# oshcamp23-badge-RevA2.net
KiCad netlist of a schematic drawn in EAGLE
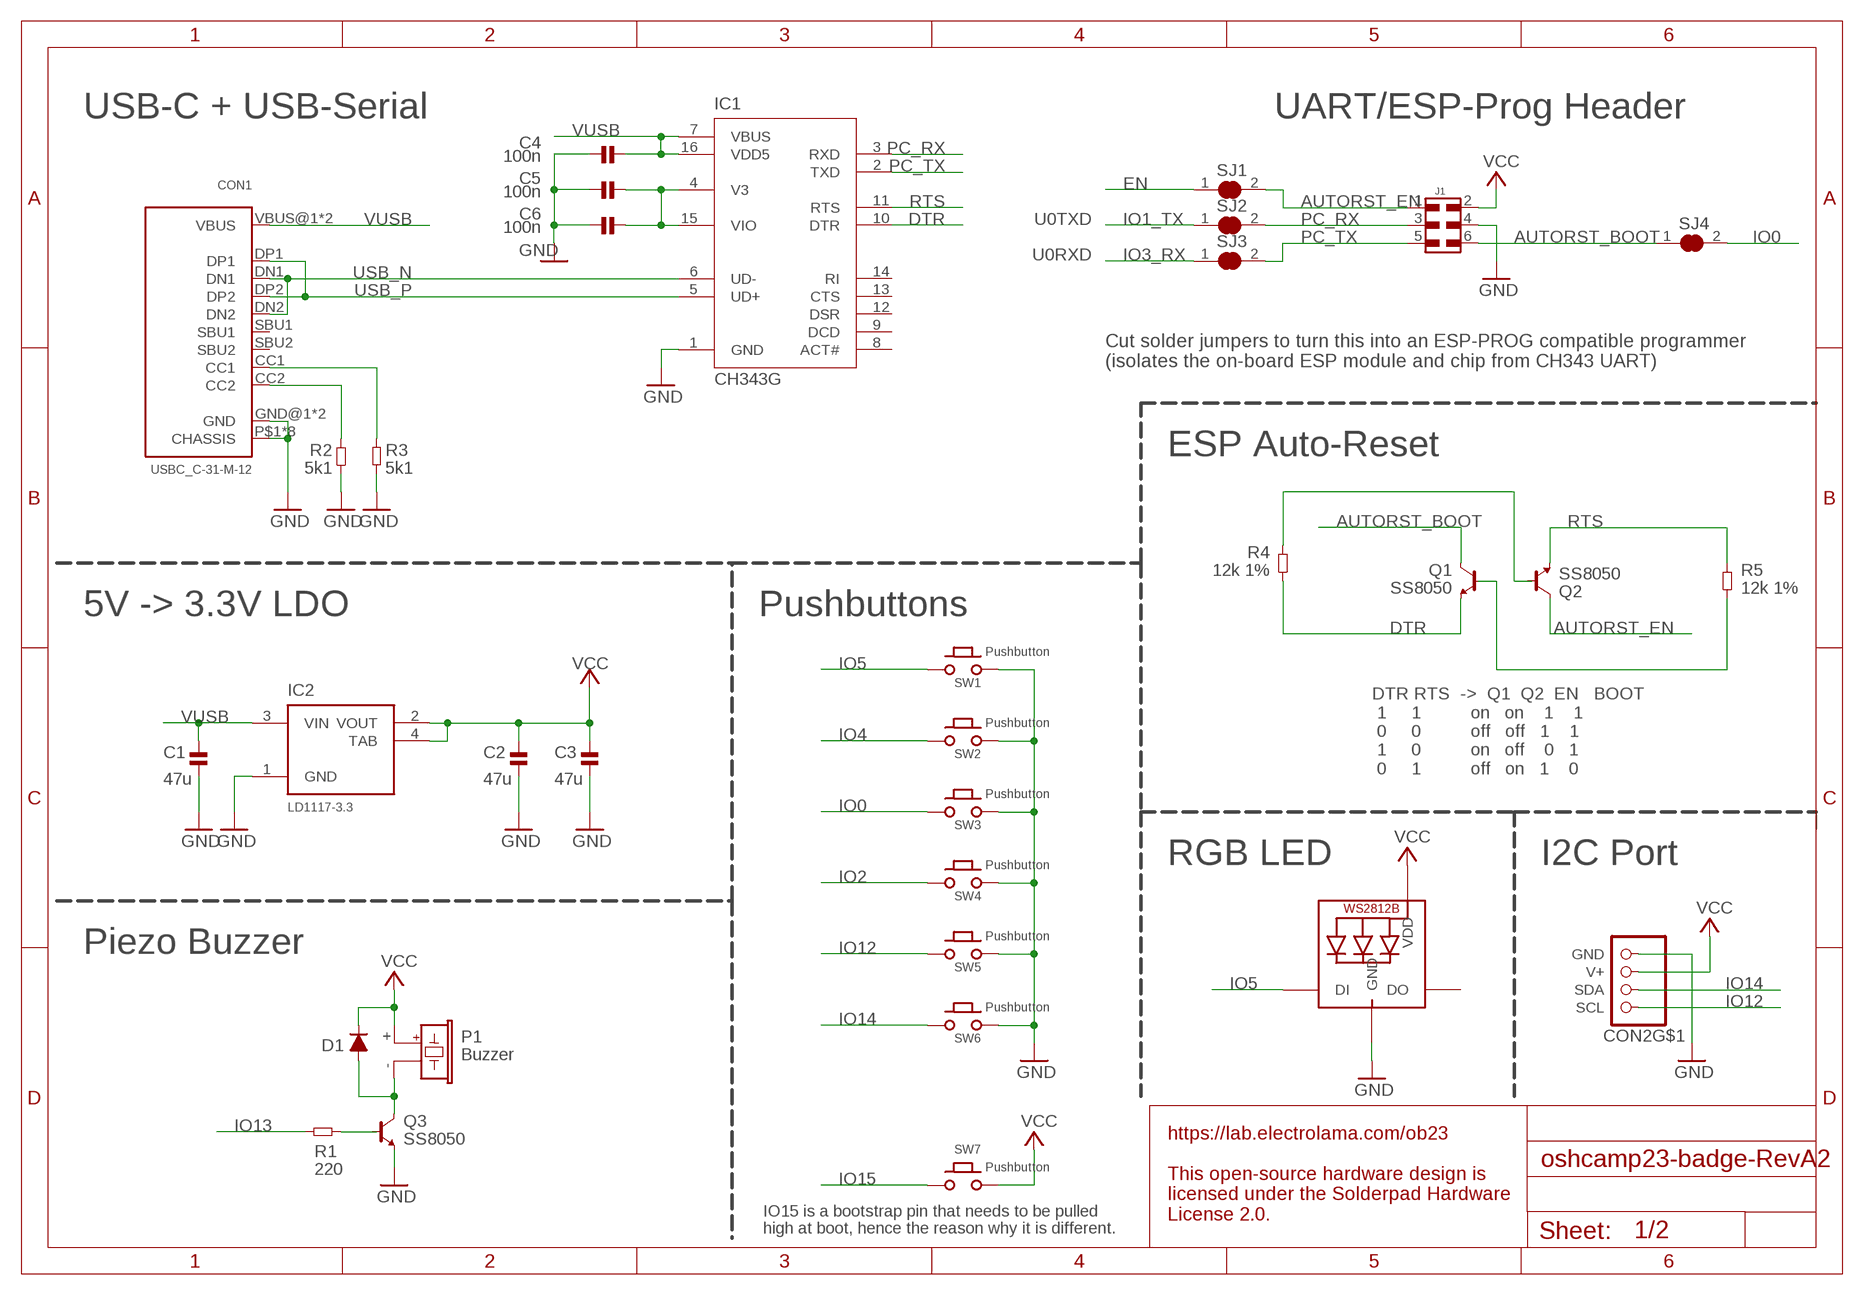
[diagram p0: schematic, sheet 1]
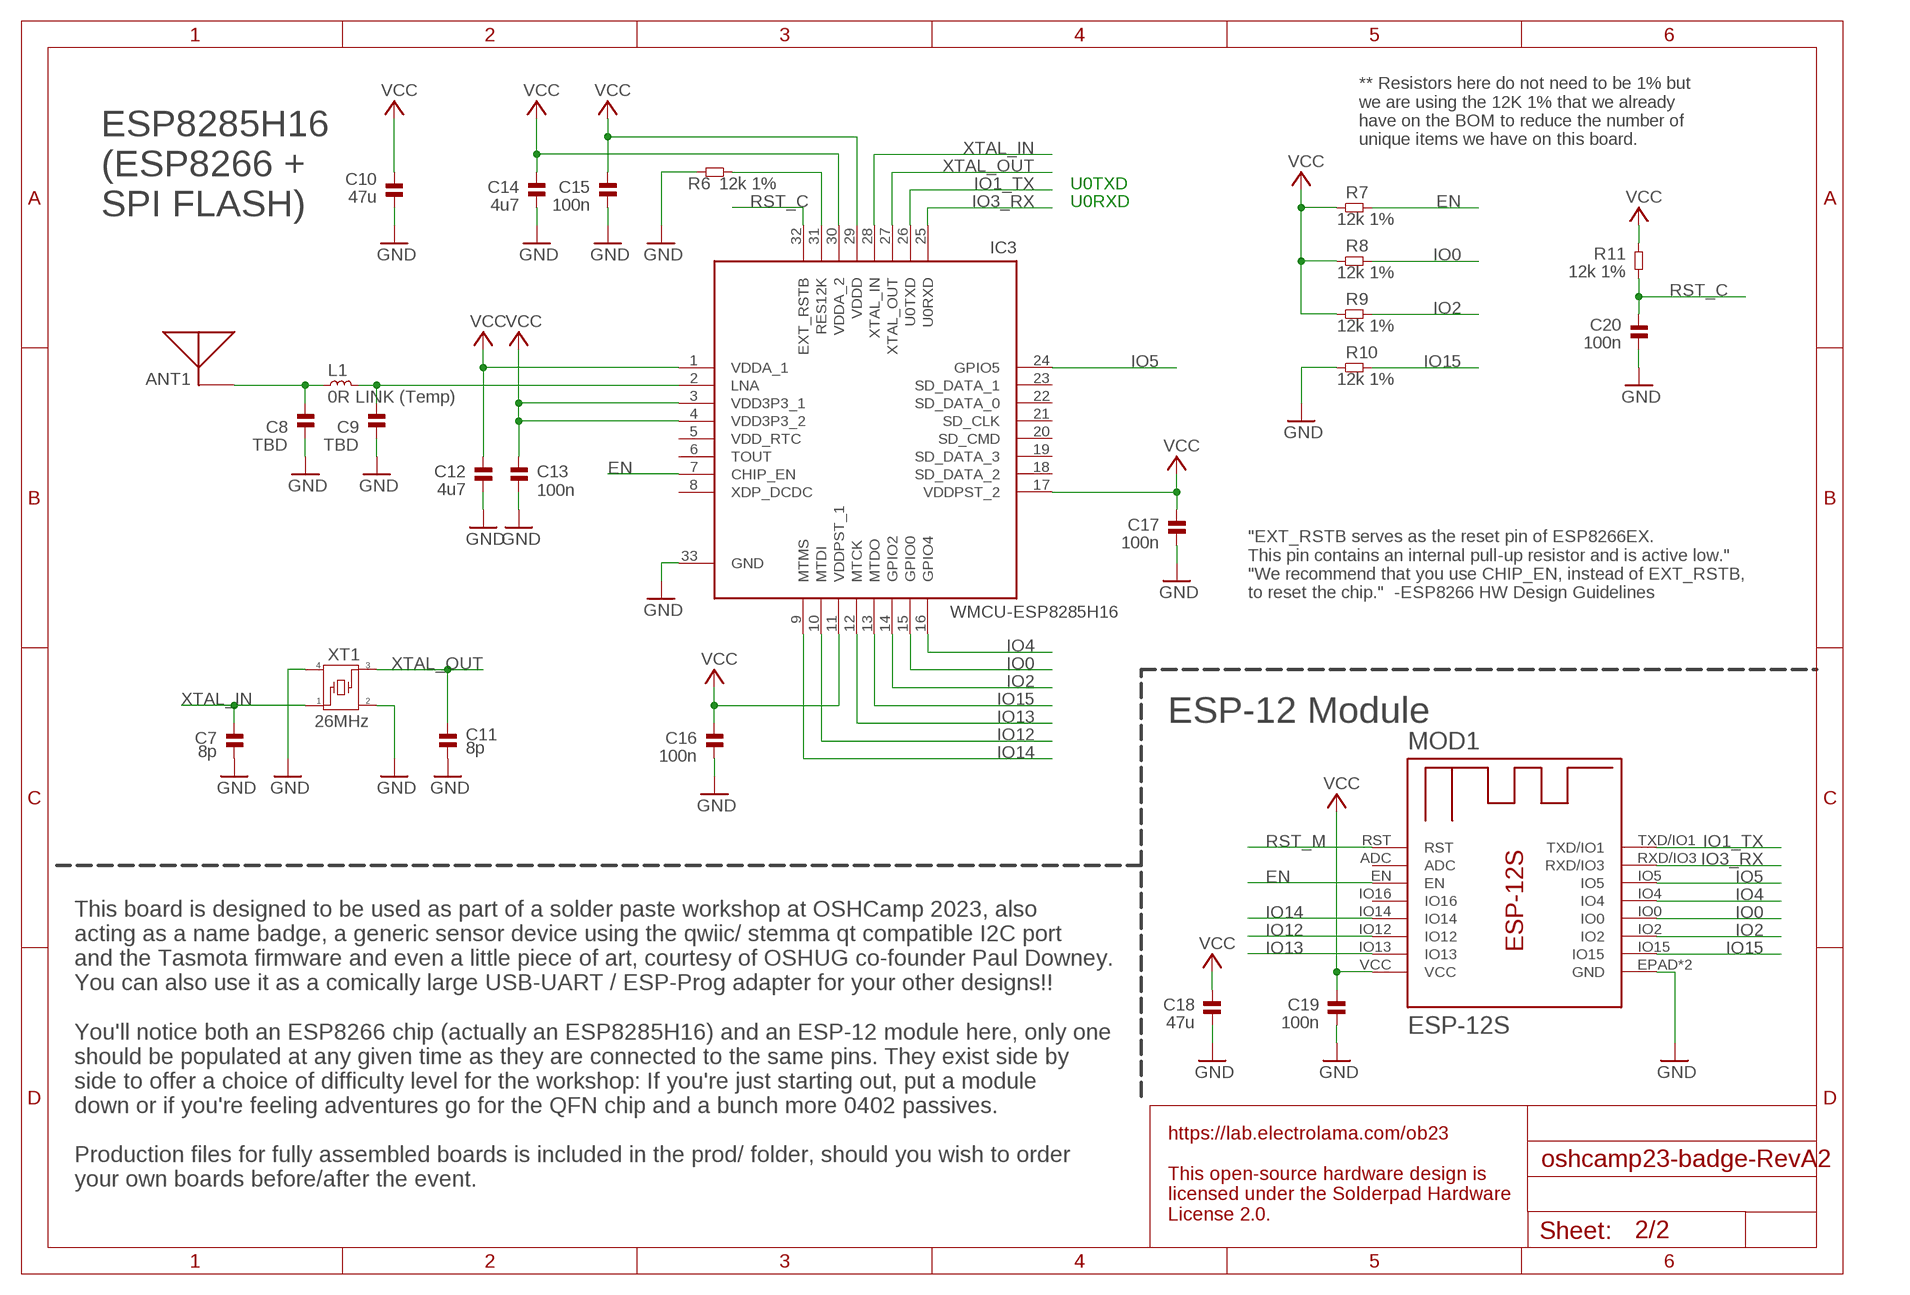
[diagram p1: schematic, sheet 2]

(export (version "E")
  (design (tool "Eeschema 10.0.6"))
  (components
    (comp (ref "C1")
      (value "47u")
      (footprint "eagle-import:_PKG_C_1206")
      (fields (field (name "MPN") "CL31A476MPHNNNE"))
      (libsource (lib "eagle-import") (part "CAP-1206"))
    )
    (comp (ref "C2")
      (value "47u")
      (footprint "eagle-import:_PKG_C_1206")
      (fields (field (name "MPN") "CL31A476MPHNNNE"))
      (libsource (lib "eagle-import") (part "CAP-1206"))
    )
    (comp (ref "C3")
      (value "47u")
      (footprint "eagle-import:_PKG_C_1206")
      (fields (field (name "MPN") "CL31A476MPHNNNE"))
      (libsource (lib "eagle-import") (part "CAP-1206"))
    )
    (comp (ref "C4")
      (value "100n")
      (footprint "eagle-import:_PKG_C_0402")
      (libsource (lib "eagle-import") (part "CAP-0402"))
    )
    (comp (ref "C5")
      (value "100n")
      (footprint "eagle-import:_PKG_C_0402")
      (libsource (lib "eagle-import") (part "CAP-0402"))
    )
    (comp (ref "C6")
      (value "100n")
      (footprint "eagle-import:_PKG_C_0402")
      (libsource (lib "eagle-import") (part "CAP-0402"))
    )
    (comp (ref "CON1")
      (value "USBC_C-31-M-12")
      (footprint "eagle-import:USBC_C-31-M-12")
      (libsource (lib "eagle-import") (part "USBC_USB-C-12"))
    )
    (comp (ref "CON2")
      (value "STEMMA_I2C_QT")
      (footprint "eagle-import:JST_SH4")
      (libsource (lib "eagle-import") (part "STEMMA_I2C_QT"))
    )
    (comp (ref "D1")
      (value "DIODE-SWITCHING-1N4148W")
      (footprint "eagle-import:_PKG_SOD123")
      (libsource (lib "eagle-import") (part "DIODE-SWITCHING-1N4148W"))
    )
    (comp (ref "IC1")
      (value "CH343G")
      (footprint "eagle-import:_PKG_SOP16")
      (libsource (lib "eagle-import") (part "INTERFACE-CH343G"))
    )
    (comp (ref "IC2")
      (value "LD1117-3.3")
      (footprint "eagle-import:_PKG_SOT223-4_TI-DCY4")
      (libsource (lib "eagle-import") (part "POWER-LDO-LD1117-SOT223-4"))
    )
    (comp (ref "J1")
      (value "61030621121")
      (footprint "eagle-import:61030621121")
      (libsource (lib "eagle-import") (part "6103XX21121_61030621121"))
    )
    (comp (ref "LED1")
      (value "WS2812B5050")
      (footprint "eagle-import:WS2812B")
      (libsource (lib "eagle-import") (part "WS2812B5050"))
    )
    (comp (ref "P1")
      (value "Buzzer")
      (footprint "eagle-import:MLT-8530")
      (libsource (lib "eagle-import") (part "PIEZO-MLT-8530"))
    )
    (comp (ref "Q1")
      (value "SS8050")
      (footprint "eagle-import:SOT96P237X111-3N")
      (fields
        (field (name "ARROW_PART_NUMBER") "MMBT5550LT1G")
        (field (name "MOUSER_PART_NUMBER") "863-MMBT5550LT1G")
      )
      (libsource (lib "eagle-import") (part "NPN-MMBT5550LT1G"))
    )
    (comp (ref "Q2")
      (value "SS8050")
      (footprint "eagle-import:SOT96P237X111-3N")
      (fields
        (field (name "ARROW_PART_NUMBER") "MMBT5550LT1G")
        (field (name "MOUSER_PART_NUMBER") "863-MMBT5550LT1G")
      )
      (libsource (lib "eagle-import") (part "NPN-MMBT5550LT1G"))
    )
    (comp (ref "Q3")
      (value "SS8050")
      (footprint "eagle-import:SOT96P237X111-3N")
      (fields
        (field (name "ARROW_PART_NUMBER") "MMBT5550LT1G")
        (field (name "MOUSER_PART_NUMBER") "863-MMBT5550LT1G")
      )
      (libsource (lib "eagle-import") (part "NPN-MMBT5550LT1G"))
    )
    (comp (ref "R1")
      (value "220")
      (footprint "eagle-import:_PKG_R_0603")
      (libsource (lib "eagle-import") (part "RES-0603"))
    )
    (comp (ref "R2")
      (value "5k1")
      (footprint "eagle-import:_PKG_R_0603")
      (libsource (lib "eagle-import") (part "RES-0603"))
    )
    (comp (ref "R3")
      (value "5k1")
      (footprint "eagle-import:_PKG_R_0603")
      (libsource (lib "eagle-import") (part "RES-0603"))
    )
    (comp (ref "R4")
      (value "12k 1%")
      (footprint "eagle-import:_PKG_R_0402")
      (libsource (lib "eagle-import") (part "RES-0402"))
    )
    (comp (ref "R5")
      (value "12k 1%")
      (footprint "eagle-import:_PKG_R_0402")
      (libsource (lib "eagle-import") (part "RES-0402"))
    )
    (comp (ref "SJ1")
      (value "SJ-SHORT")
      (footprint "eagle-import:SJ-SHORT")
      (libsource (lib "eagle-import") (part "SJ-SHORT"))
    )
    (comp (ref "SJ2")
      (value "SJ-SHORT")
      (footprint "eagle-import:SJ-SHORT")
      (libsource (lib "eagle-import") (part "SJ-SHORT"))
    )
    (comp (ref "SJ3")
      (value "SJ-SHORT")
      (footprint "eagle-import:SJ-SHORT")
      (libsource (lib "eagle-import") (part "SJ-SHORT"))
    )
    (comp (ref "SJ4")
      (value "SJ-SHORT")
      (footprint "eagle-import:SJ-SHORT")
      (libsource (lib "eagle-import") (part "SJ-SHORT"))
    )
    (comp (ref "SW1")
      (value "Pushbutton")
      (footprint "eagle-import:GENERIC_SPNO_4P_6X6MM")
      (libsource (lib "eagle-import") (part "PUSHBUTTON-6X6MM"))
    )
    (comp (ref "SW2")
      (value "Pushbutton")
      (footprint "eagle-import:GENERIC_SPNO_4P_6X6MM")
      (libsource (lib "eagle-import") (part "PUSHBUTTON-6X6MM"))
    )
    (comp (ref "SW3")
      (value "Pushbutton")
      (footprint "eagle-import:GENERIC_SPNO_4P_6X6MM")
      (libsource (lib "eagle-import") (part "PUSHBUTTON-6X6MM"))
    )
    (comp (ref "SW4")
      (value "Pushbutton")
      (footprint "eagle-import:GENERIC_SPNO_4P_6X6MM")
      (libsource (lib "eagle-import") (part "PUSHBUTTON-6X6MM"))
    )
    (comp (ref "SW5")
      (value "Pushbutton")
      (footprint "eagle-import:GENERIC_SPNO_4P_6X6MM")
      (libsource (lib "eagle-import") (part "PUSHBUTTON-6X6MM"))
    )
    (comp (ref "SW6")
      (value "Pushbutton")
      (footprint "eagle-import:GENERIC_SPNO_4P_6X6MM")
      (libsource (lib "eagle-import") (part "PUSHBUTTON-6X6MM"))
    )
    (comp (ref "SW7")
      (value "Pushbutton")
      (footprint "eagle-import:GENERIC_SPNO_4P_6X6MM")
      (libsource (lib "eagle-import") (part "PUSHBUTTON-6X6MM"))
    )
    (comp (ref "ANT1")
      (value "ANT3216LL00R2400A")
      (footprint "eagle-import:YAGEO-ANT3216LL00R2400A")
      (libsource (lib "eagle-import") (part "ANT-CERAMIC-YAGEO-ANT3216LL00R2400A"))
    )
    (comp (ref "C7")
      (value "8p")
      (footprint "eagle-import:_PKG_C_0402")
      (libsource (lib "eagle-import") (part "CAP-0402"))
    )
    (comp (ref "C8")
      (value "TBD")
      (footprint "eagle-import:_PKG_C_0402_NOTHERMALS")
      (libsource (lib "eagle-import") (part "CAP-0402-NOTHERMALS"))
    )
    (comp (ref "C9")
      (value "TBD")
      (footprint "eagle-import:_PKG_C_0402_NOTHERMALS")
      (libsource (lib "eagle-import") (part "CAP-0402-NOTHERMALS"))
    )
    (comp (ref "C10")
      (value "47u")
      (footprint "eagle-import:_PKG_C_1206")
      (fields (field (name "MPN") "CL31A476MPHNNNE"))
      (libsource (lib "eagle-import") (part "CAP-1206"))
    )
    (comp (ref "C11")
      (value "8p")
      (footprint "eagle-import:_PKG_C_0402")
      (libsource (lib "eagle-import") (part "CAP-0402"))
    )
    (comp (ref "C12")
      (value "4u7")
      (footprint "eagle-import:_PKG_C_0402_NOTHERMALS")
      (libsource (lib "eagle-import") (part "CAP-0402-NOTHERMALS"))
    )
    (comp (ref "C13")
      (value "100n")
      (footprint "eagle-import:_PKG_C_0402_NOTHERMALS")
      (libsource (lib "eagle-import") (part "CAP-0402-NOTHERMALS"))
    )
    (comp (ref "C14")
      (value "4u7")
      (footprint "eagle-import:_PKG_C_0402_NOTHERMALS")
      (libsource (lib "eagle-import") (part "CAP-0402-NOTHERMALS"))
    )
    (comp (ref "C15")
      (value "100n")
      (footprint "eagle-import:_PKG_C_0402_NOTHERMALS")
      (libsource (lib "eagle-import") (part "CAP-0402-NOTHERMALS"))
    )
    (comp (ref "C16")
      (value "100n")
      (footprint "eagle-import:_PKG_C_0402_NOTHERMALS")
      (libsource (lib "eagle-import") (part "CAP-0402-NOTHERMALS"))
    )
    (comp (ref "C17")
      (value "100n")
      (footprint "eagle-import:_PKG_C_0402_NOTHERMALS")
      (libsource (lib "eagle-import") (part "CAP-0402-NOTHERMALS"))
    )
    (comp (ref "C18")
      (value "47u")
      (footprint "eagle-import:_PKG_C_1206")
      (fields (field (name "MPN") "CL31A476MPHNNNE"))
      (libsource (lib "eagle-import") (part "CAP-1206"))
    )
    (comp (ref "C19")
      (value "100n")
      (footprint "eagle-import:_PKG_C_0402")
      (libsource (lib "eagle-import") (part "CAP-0402"))
    )
    (comp (ref "C20")
      (value "100n")
      (footprint "eagle-import:_PKG_C_0402_NOTHERMALS")
      (libsource (lib "eagle-import") (part "CAP-0402-NOTHERMALS"))
    )
    (comp (ref "IC3")
      (value "WMCU-ESP8285H16")
      (footprint "eagle-import:QFN50P500X500X90-33N")
      (fields
        (field (name "MANUFACTURER_PART_NUMBER") "ESP8285H16")
        (field (name "MOUSER_PART_NUMBER") "356-ESP8285H16")
      )
      (libsource (lib "eagle-import") (part "WMCU-ESP8285H16"))
    )
    (comp (ref "L1")
      (value "0R LINK (Temp)")
      (footprint "eagle-import:_PKG_L_0402")
      (libsource (lib "eagle-import") (part "INDUCTOR-0402"))
    )
    (comp (ref "MOD1")
      (value "ESP-12S")
      (footprint "eagle-import:ESP-12S")
      (libsource (lib "eagle-import") (part "MODULE_ESP-12S"))
    )
    (comp (ref "R6")
      (value "12k 1%")
      (footprint "eagle-import:_PKG_R_0402")
      (libsource (lib "eagle-import") (part "RES-0402"))
    )
    (comp (ref "R7")
      (value "12k 1%")
      (footprint "eagle-import:_PKG_R_0402")
      (libsource (lib "eagle-import") (part "RES-0402"))
    )
    (comp (ref "R8")
      (value "12k 1%")
      (footprint "eagle-import:_PKG_R_0402")
      (libsource (lib "eagle-import") (part "RES-0402"))
    )
    (comp (ref "R9")
      (value "12k 1%")
      (footprint "eagle-import:_PKG_R_0402")
      (libsource (lib "eagle-import") (part "RES-0402"))
    )
    (comp (ref "R10")
      (value "12k 1%")
      (footprint "eagle-import:_PKG_R_0402")
      (libsource (lib "eagle-import") (part "RES-0402"))
    )
    (comp (ref "R11")
      (value "12k 1%")
      (footprint "eagle-import:_PKG_R_0402")
      (libsource (lib "eagle-import") (part "RES-0402"))
    )
    (comp (ref "XT1")
      (value "26MHz")
      (footprint "eagle-import:XTAL-4P-2016")
      (libsource (lib "eagle-import") (part "XTAL-4P-2016"))
    )
  )
  (nets
    (net (code "1") (name "AUTORST_BOOT") (class "Default")
      (node (ref "J1") (pin "6") (pinfunction "6_6") (pintype "passive"))
      (node (ref "Q1") (pin "3") (pinfunction "C_3") (pintype "passive"))
      (node (ref "SJ4") (pin "1") (pinfunction "1_1") (pintype "passive"))
    )
    (net (code "2") (name "AUTORST_EN") (class "Default")
      (node (ref "J1") (pin "1") (pinfunction "1_1") (pintype "passive"))
      (node (ref "Q2") (pin "3") (pinfunction "C_3") (pintype "passive"))
      (node (ref "SJ1") (pin "2") (pinfunction "2_2") (pintype "passive"))
    )
    (net (code "3") (name "DTR") (class "Default")
      (node (ref "IC1") (pin "10") (pinfunction "DTR_10") (pintype "bidirectional"))
      (node (ref "Q1") (pin "2") (pinfunction "E_2") (pintype "passive"))
      (node (ref "R4") (pin "1") (pinfunction "1_1") (pintype "passive"))
    )
    (net (code "4") (name "EN") (class "Default")
      (node (ref "IC3") (pin "7") (pinfunction "CHIP_EN_7") (pintype "bidirectional"))
      (node (ref "MOD1") (pin "EN") (pinfunction "EN_EN") (pintype "bidirectional"))
      (node (ref "R7") (pin "2") (pinfunction "2_2") (pintype "passive"))
      (node (ref "SJ1") (pin "1") (pinfunction "1_1") (pintype "passive"))
    )
    (net (code "5") (name "GND") (class "Default")
      (node (ref "C1") (pin "2") (pinfunction "2_2") (pintype "passive"))
      (node (ref "C10") (pin "2") (pinfunction "2_2") (pintype "passive"))
      (node (ref "C11") (pin "1") (pinfunction "1_1") (pintype "passive"))
      (node (ref "C12") (pin "1") (pinfunction "1_1") (pintype "passive"))
      (node (ref "C13") (pin "1") (pinfunction "1_1") (pintype "passive"))
      (node (ref "C14") (pin "1") (pinfunction "1_1") (pintype "passive"))
      (node (ref "C15") (pin "1") (pinfunction "1_1") (pintype "passive"))
      (node (ref "C16") (pin "1") (pinfunction "1_1") (pintype "passive"))
      (node (ref "C17") (pin "1") (pinfunction "1_1") (pintype "passive"))
      (node (ref "C18") (pin "2") (pinfunction "2_2") (pintype "passive"))
      (node (ref "C19") (pin "2") (pinfunction "2_2") (pintype "passive"))
      (node (ref "C2") (pin "2") (pinfunction "2_2") (pintype "passive"))
      (node (ref "C20") (pin "1") (pinfunction "1_1") (pintype "passive"))
      (node (ref "C3") (pin "2") (pinfunction "2_2") (pintype "passive"))
      (node (ref "C4") (pin "2") (pinfunction "2_2") (pintype "passive"))
      (node (ref "C5") (pin "2") (pinfunction "2_2") (pintype "passive"))
      (node (ref "C6") (pin "2") (pinfunction "2_2") (pintype "passive"))
      (node (ref "C7") (pin "1") (pinfunction "1_1") (pintype "passive"))
      (node (ref "C8") (pin "1") (pinfunction "1_1") (pintype "passive"))
      (node (ref "C9") (pin "1") (pinfunction "1_1") (pintype "passive"))
      (node (ref "CON1") (pin "GND@1") (pinfunction "GND_GND@1") (pintype "bidirectional"))
      (node (ref "CON1") (pin "GND@2") (pinfunction "GND_GND@2") (pintype "bidirectional"))
      (node (ref "CON1") (pin "P$1") (pinfunction "CHASSIS_P$1") (pintype "bidirectional"))
      (node (ref "CON1") (pin "P$2") (pinfunction "CHASSIS_P$2") (pintype "bidirectional"))
      (node (ref "CON1") (pin "P$3") (pinfunction "CHASSIS_P$3") (pintype "bidirectional"))
      (node (ref "CON1") (pin "P$4") (pinfunction "CHASSIS_P$4") (pintype "bidirectional"))
      (node (ref "CON1") (pin "P$5") (pinfunction "CHASSIS_P$5") (pintype "bidirectional"))
      (node (ref "CON1") (pin "P$6") (pinfunction "CHASSIS_P$6") (pintype "bidirectional"))
      (node (ref "CON1") (pin "P$7") (pinfunction "CHASSIS_P$7") (pintype "bidirectional"))
      (node (ref "CON1") (pin "P$8") (pinfunction "CHASSIS_P$8") (pintype "bidirectional"))
      (node (ref "CON2") (pin "1") (pinfunction "GND_1") (pintype "passive"))
      (node (ref "IC1") (pin "1") (pinfunction "GND_1") (pintype "bidirectional"))
      (node (ref "IC2") (pin "1") (pinfunction "GND_1") (pintype "output"))
      (node (ref "IC3") (pin "33") (pinfunction "GND_33") (pintype "bidirectional"))
      (node (ref "J1") (pin "4") (pinfunction "4_4") (pintype "passive"))
      (node (ref "LED1") (pin "3-GND") (pinfunction "GND_3-GND") (pintype "power_in"))
      (node (ref "MOD1") (pin "EPAD") (pinfunction "GND_EPAD") (pintype "power_in"))
      (node (ref "MOD1") (pin "GND") (pinfunction "GND_GND") (pintype "power_in"))
      (node (ref "Q3") (pin "2") (pinfunction "E_2") (pintype "passive"))
      (node (ref "R10") (pin "1") (pinfunction "1_1") (pintype "passive"))
      (node (ref "R2") (pin "1") (pinfunction "1_1") (pintype "passive"))
      (node (ref "R3") (pin "1") (pinfunction "1_1") (pintype "passive"))
      (node (ref "R6") (pin "2") (pinfunction "2_2") (pintype "passive"))
      (node (ref "SW1") (pin "P$3") (pinfunction "2_P$3") (pintype "bidirectional"))
      (node (ref "SW1") (pin "P$4") (pinfunction "2_P$4") (pintype "bidirectional"))
      (node (ref "SW2") (pin "P$3") (pinfunction "2_P$3") (pintype "bidirectional"))
      (node (ref "SW2") (pin "P$4") (pinfunction "2_P$4") (pintype "bidirectional"))
      (node (ref "SW3") (pin "P$3") (pinfunction "2_P$3") (pintype "bidirectional"))
      (node (ref "SW3") (pin "P$4") (pinfunction "2_P$4") (pintype "bidirectional"))
      (node (ref "SW4") (pin "P$3") (pinfunction "2_P$3") (pintype "bidirectional"))
      (node (ref "SW4") (pin "P$4") (pinfunction "2_P$4") (pintype "bidirectional"))
      (node (ref "SW5") (pin "P$3") (pinfunction "2_P$3") (pintype "bidirectional"))
      (node (ref "SW5") (pin "P$4") (pinfunction "2_P$4") (pintype "bidirectional"))
      (node (ref "SW6") (pin "P$3") (pinfunction "2_P$3") (pintype "bidirectional"))
      (node (ref "SW6") (pin "P$4") (pinfunction "2_P$4") (pintype "bidirectional"))
      (node (ref "XT1") (pin "2") (pinfunction "2_2") (pintype "bidirectional"))
      (node (ref "XT1") (pin "4") (pinfunction "4_4") (pintype "bidirectional"))
    )
    (net (code "6") (name "IO0") (class "Default")
      (node (ref "IC3") (pin "15") (pinfunction "GPIO0_15") (pintype "bidirectional"))
      (node (ref "MOD1") (pin "IO0") (pinfunction "IO0_IO0") (pintype "bidirectional"))
      (node (ref "R8") (pin "2") (pinfunction "2_2") (pintype "passive"))
      (node (ref "SJ4") (pin "2") (pinfunction "2_2") (pintype "passive"))
      (node (ref "SW3") (pin "P$1") (pinfunction "1_P$1") (pintype "bidirectional"))
      (node (ref "SW3") (pin "P$2") (pinfunction "1_P$2") (pintype "bidirectional"))
    )
    (net (code "7") (name "IO1_TX") (class "Default")
      (node (ref "IC3") (pin "26") (pinfunction "U0TXD_26") (pintype "bidirectional"))
      (node (ref "MOD1") (pin "TXD/IO1") (pinfunction "TXD/IO1_TXD/IO1") (pintype "bidirectional"))
      (node (ref "SJ2") (pin "1") (pinfunction "1_1") (pintype "passive"))
    )
    (net (code "8") (name "IO2") (class "Default")
      (node (ref "IC3") (pin "14") (pinfunction "GPIO2_14") (pintype "bidirectional"))
      (node (ref "MOD1") (pin "IO2") (pinfunction "IO2_IO2") (pintype "bidirectional"))
      (node (ref "R9") (pin "2") (pinfunction "2_2") (pintype "passive"))
      (node (ref "SW4") (pin "P$1") (pinfunction "1_P$1") (pintype "bidirectional"))
      (node (ref "SW4") (pin "P$2") (pinfunction "1_P$2") (pintype "bidirectional"))
    )
    (net (code "9") (name "IO3_RX") (class "Default")
      (node (ref "IC3") (pin "25") (pinfunction "U0RXD_25") (pintype "bidirectional"))
      (node (ref "MOD1") (pin "RXD/IO3") (pinfunction "RXD/IO3_RXD/IO3") (pintype "bidirectional"))
      (node (ref "SJ3") (pin "1") (pinfunction "1_1") (pintype "passive"))
    )
    (net (code "10") (name "IO4") (class "Default")
      (node (ref "IC3") (pin "16") (pinfunction "GPIO4_16") (pintype "bidirectional"))
      (node (ref "MOD1") (pin "IO4") (pinfunction "IO4_IO4") (pintype "bidirectional"))
      (node (ref "SW2") (pin "P$1") (pinfunction "1_P$1") (pintype "bidirectional"))
      (node (ref "SW2") (pin "P$2") (pinfunction "1_P$2") (pintype "bidirectional"))
    )
    (net (code "11") (name "IO5") (class "Default")
      (node (ref "IC3") (pin "24") (pinfunction "GPIO5_24") (pintype "bidirectional"))
      (node (ref "LED1") (pin "4-DIN") (pinfunction "DI_4-DIN") (pintype "input"))
      (node (ref "MOD1") (pin "IO5") (pinfunction "IO5_IO5") (pintype "bidirectional"))
      (node (ref "SW1") (pin "P$1") (pinfunction "1_P$1") (pintype "bidirectional"))
      (node (ref "SW1") (pin "P$2") (pinfunction "1_P$2") (pintype "bidirectional"))
    )
    (net (code "12") (name "IO12") (class "Default")
      (node (ref "CON2") (pin "4") (pinfunction "SCL_4") (pintype "passive"))
      (node (ref "IC3") (pin "10") (pinfunction "MTDI_10") (pintype "bidirectional"))
      (node (ref "MOD1") (pin "IO12") (pinfunction "IO12_IO12") (pintype "bidirectional"))
      (node (ref "SW5") (pin "P$1") (pinfunction "1_P$1") (pintype "bidirectional"))
      (node (ref "SW5") (pin "P$2") (pinfunction "1_P$2") (pintype "bidirectional"))
    )
    (net (code "13") (name "IO13") (class "Default")
      (node (ref "IC3") (pin "12") (pinfunction "MTCK_12") (pintype "bidirectional"))
      (node (ref "MOD1") (pin "IO13") (pinfunction "IO13_IO13") (pintype "bidirectional"))
      (node (ref "R1") (pin "2") (pinfunction "2_2") (pintype "passive"))
    )
    (net (code "14") (name "IO14") (class "Default")
      (node (ref "CON2") (pin "3") (pinfunction "SDA_3") (pintype "passive"))
      (node (ref "IC3") (pin "9") (pinfunction "MTMS_9") (pintype "bidirectional"))
      (node (ref "MOD1") (pin "IO14") (pinfunction "IO14_IO14") (pintype "bidirectional"))
      (node (ref "SW6") (pin "P$1") (pinfunction "1_P$1") (pintype "bidirectional"))
      (node (ref "SW6") (pin "P$2") (pinfunction "1_P$2") (pintype "bidirectional"))
    )
    (net (code "15") (name "IO15") (class "Default")
      (node (ref "IC3") (pin "13") (pinfunction "MTDO_13") (pintype "bidirectional"))
      (node (ref "MOD1") (pin "IO15") (pinfunction "IO15_IO15") (pintype "bidirectional"))
      (node (ref "R10") (pin "2") (pinfunction "2_2") (pintype "passive"))
      (node (ref "SW7") (pin "P$1") (pinfunction "1_P$1") (pintype "bidirectional"))
      (node (ref "SW7") (pin "P$2") (pinfunction "1_P$2") (pintype "bidirectional"))
    )
    (net (code "16") (name "Net-(ANT1-FEED)") (class "Default")
      (node (ref "ANT1") (pin "S1") (pinfunction "FEED_S1") (pintype "bidirectional"))
      (node (ref "C8") (pin "2") (pinfunction "2_2") (pintype "passive"))
      (node (ref "L1") (pin "1") (pinfunction "1_1") (pintype "passive"))
    )
    (net (code "17") (name "Net-(CON1-PadCC1)") (class "Default")
      (node (ref "CON1") (pin "CC1") (pinfunction "CC1_CC1") (pintype "bidirectional"))
      (node (ref "R3") (pin "2") (pinfunction "2_2") (pintype "passive"))
    )
    (net (code "18") (name "Net-(CON1-PadCC2)") (class "Default")
      (node (ref "CON1") (pin "CC2") (pinfunction "CC2_CC2") (pintype "bidirectional"))
      (node (ref "R2") (pin "2") (pinfunction "2_2") (pintype "passive"))
    )
    (net (code "19") (name "Net-(D1-A)") (class "Default")
      (node (ref "D1") (pin "2") (pinfunction "A_2") (pintype "passive"))
      (node (ref "P1") (pin "-") (pinfunction "-_-") (pintype "passive"))
      (node (ref "Q3") (pin "3") (pinfunction "C_3") (pintype "passive"))
    )
    (net (code "20") (name "Net-(IC1-V3)") (class "Default")
      (node (ref "C5") (pin "1") (pinfunction "1_1") (pintype "passive"))
      (node (ref "C6") (pin "1") (pinfunction "1_1") (pintype "passive"))
      (node (ref "IC1") (pin "15") (pinfunction "VIO_15") (pintype "bidirectional"))
      (node (ref "IC1") (pin "4") (pinfunction "V3_4") (pintype "bidirectional"))
    )
    (net (code "21") (name "Net-(IC3-LNA)") (class "Default")
      (node (ref "C9") (pin "2") (pinfunction "2_2") (pintype "passive"))
      (node (ref "IC3") (pin "2") (pinfunction "LNA_2") (pintype "bidirectional"))
      (node (ref "L1") (pin "2") (pinfunction "2_2") (pintype "passive"))
    )
    (net (code "22") (name "Net-(IC3-RES12K)") (class "Default")
      (node (ref "IC3") (pin "31") (pinfunction "RES12K_31") (pintype "bidirectional"))
      (node (ref "R6") (pin "1") (pinfunction "1_1") (pintype "passive"))
    )
    (net (code "23") (name "Net-(Q1-B)") (class "Default")
      (node (ref "Q1") (pin "1") (pinfunction "B_1") (pintype "passive"))
      (node (ref "R5") (pin "1") (pinfunction "1_1") (pintype "passive"))
    )
    (net (code "24") (name "Net-(Q2-B)") (class "Default")
      (node (ref "Q2") (pin "1") (pinfunction "B_1") (pintype "passive"))
      (node (ref "R4") (pin "2") (pinfunction "2_2") (pintype "passive"))
    )
    (net (code "25") (name "Net-(Q3-B)") (class "Default")
      (node (ref "Q3") (pin "1") (pinfunction "B_1") (pintype "passive"))
      (node (ref "R1") (pin "1") (pinfunction "1_1") (pintype "passive"))
    )
    (net (code "26") (name "PC_RX") (class "Default")
      (node (ref "IC1") (pin "3") (pinfunction "RXD_3") (pintype "bidirectional"))
      (node (ref "J1") (pin "3") (pinfunction "3_3") (pintype "passive"))
      (node (ref "SJ2") (pin "2") (pinfunction "2_2") (pintype "passive"))
    )
    (net (code "27") (name "PC_TX") (class "Default")
      (node (ref "IC1") (pin "2") (pinfunction "TXD_2") (pintype "bidirectional"))
      (node (ref "J1") (pin "5") (pinfunction "5_5") (pintype "passive"))
      (node (ref "SJ3") (pin "2") (pinfunction "2_2") (pintype "passive"))
    )
    (net (code "28") (name "RST_C") (class "Default")
      (node (ref "C20") (pin "2") (pinfunction "2_2") (pintype "passive"))
      (node (ref "IC3") (pin "32") (pinfunction "EXT_RSTB_32") (pintype "bidirectional"))
      (node (ref "R11") (pin "1") (pinfunction "1_1") (pintype "passive"))
    )
    (net (code "29") (name "RST_M") (class "Default")
      (node (ref "MOD1") (pin "RST") (pinfunction "RST_RST") (pintype "input"))
    )
    (net (code "30") (name "RTS") (class "Default")
      (node (ref "IC1") (pin "11") (pinfunction "RTS_11") (pintype "bidirectional"))
      (node (ref "Q2") (pin "2") (pinfunction "E_2") (pintype "passive"))
      (node (ref "R5") (pin "2") (pinfunction "2_2") (pintype "passive"))
    )
    (net (code "31") (name "USB_N") (class "Default")
      (node (ref "CON1") (pin "DN1") (pinfunction "DN1_DN1") (pintype "bidirectional"))
      (node (ref "CON1") (pin "DN2") (pinfunction "DN2_DN2") (pintype "bidirectional"))
      (node (ref "IC1") (pin "6") (pinfunction "UD-_6") (pintype "bidirectional"))
    )
    (net (code "32") (name "USB_P") (class "Default")
      (node (ref "CON1") (pin "DP1") (pinfunction "DP1_DP1") (pintype "bidirectional"))
      (node (ref "CON1") (pin "DP2") (pinfunction "DP2_DP2") (pintype "bidirectional"))
      (node (ref "IC1") (pin "5") (pinfunction "UD+_5") (pintype "bidirectional"))
    )
    (net (code "33") (name "VCC") (class "Default")
      (node (ref "C10") (pin "1") (pinfunction "1_1") (pintype "passive"))
      (node (ref "C12") (pin "2") (pinfunction "2_2") (pintype "passive"))
      (node (ref "C13") (pin "2") (pinfunction "2_2") (pintype "passive"))
      (node (ref "C14") (pin "2") (pinfunction "2_2") (pintype "passive"))
      (node (ref "C15") (pin "2") (pinfunction "2_2") (pintype "passive"))
      (node (ref "C16") (pin "2") (pinfunction "2_2") (pintype "passive"))
      (node (ref "C17") (pin "2") (pinfunction "2_2") (pintype "passive"))
      (node (ref "C18") (pin "1") (pinfunction "1_1") (pintype "passive"))
      (node (ref "C19") (pin "1") (pinfunction "1_1") (pintype "passive"))
      (node (ref "C2") (pin "1") (pinfunction "1_1") (pintype "passive"))
      (node (ref "C3") (pin "1") (pinfunction "1_1") (pintype "passive"))
      (node (ref "CON2") (pin "2") (pinfunction "V+_2") (pintype "passive"))
      (node (ref "D1") (pin "1") (pinfunction "C_1") (pintype "passive"))
      (node (ref "IC2") (pin "2") (pinfunction "VOUT_2") (pintype "output"))
      (node (ref "IC2") (pin "4") (pinfunction "TAB_4") (pintype "output"))
      (node (ref "IC3") (pin "1") (pinfunction "VDDA_1_1") (pintype "bidirectional"))
      (node (ref "IC3") (pin "11") (pinfunction "VDDPST_1_11") (pintype "bidirectional"))
      (node (ref "IC3") (pin "17") (pinfunction "VDDPST_2_17") (pintype "bidirectional"))
      (node (ref "IC3") (pin "29") (pinfunction "VDDD_29") (pintype "bidirectional"))
      (node (ref "IC3") (pin "3") (pinfunction "VDD3P3_1_3") (pintype "bidirectional"))
      (node (ref "IC3") (pin "30") (pinfunction "VDDA_2_30") (pintype "bidirectional"))
      (node (ref "IC3") (pin "4") (pinfunction "VDD3P3_2_4") (pintype "bidirectional"))
      (node (ref "J1") (pin "2") (pinfunction "2_2") (pintype "passive"))
      (node (ref "LED1") (pin "1-VDD") (pinfunction "VDD_1-VDD") (pintype "power_in"))
      (node (ref "MOD1") (pin "VCC") (pinfunction "VCC_VCC") (pintype "power_in"))
      (node (ref "P1") (pin "+") (pinfunction "+_+") (pintype "passive"))
      (node (ref "R11") (pin "2") (pinfunction "2_2") (pintype "passive"))
      (node (ref "R7") (pin "1") (pinfunction "1_1") (pintype "passive"))
      (node (ref "R8") (pin "1") (pinfunction "1_1") (pintype "passive"))
      (node (ref "R9") (pin "1") (pinfunction "1_1") (pintype "passive"))
      (node (ref "SW7") (pin "P$3") (pinfunction "2_P$3") (pintype "bidirectional"))
      (node (ref "SW7") (pin "P$4") (pinfunction "2_P$4") (pintype "bidirectional"))
    )
    (net (code "34") (name "VUSB") (class "Default")
      (node (ref "C1") (pin "1") (pinfunction "1_1") (pintype "passive"))
      (node (ref "C4") (pin "1") (pinfunction "1_1") (pintype "passive"))
      (node (ref "CON1") (pin "VBUS@1") (pinfunction "VBUS_VBUS@1") (pintype "bidirectional"))
      (node (ref "CON1") (pin "VBUS@2") (pinfunction "VBUS_VBUS@2") (pintype "bidirectional"))
      (node (ref "IC1") (pin "16") (pinfunction "VDD5_16") (pintype "bidirectional"))
      (node (ref "IC1") (pin "7") (pinfunction "VBUS_7") (pintype "bidirectional"))
      (node (ref "IC2") (pin "3") (pinfunction "VIN_3") (pintype "output"))
    )
    (net (code "35") (name "XTAL_IN") (class "Default")
      (node (ref "C7") (pin "2") (pinfunction "2_2") (pintype "passive"))
      (node (ref "IC3") (pin "28") (pinfunction "XTAL_IN_28") (pintype "bidirectional"))
      (node (ref "XT1") (pin "1") (pinfunction "1_1") (pintype "passive"))
    )
    (net (code "36") (name "XTAL_OUT") (class "Default")
      (node (ref "C11") (pin "2") (pinfunction "2_2") (pintype "passive"))
      (node (ref "IC3") (pin "27") (pinfunction "XTAL_OUT_27") (pintype "bidirectional"))
      (node (ref "XT1") (pin "3") (pinfunction "3_3") (pintype "passive"))
    )
    (net (code "37") (name "unconnected-(CON1-PadSBU1)") (class "Default")
      (node (ref "CON1") (pin "SBU1") (pinfunction "SBU1_SBU1") (pintype "bidirectional"))
    )
    (net (code "38") (name "unconnected-(CON1-PadSBU2)") (class "Default")
      (node (ref "CON1") (pin "SBU2") (pinfunction "SBU2_SBU2") (pintype "bidirectional"))
    )
    (net (code "39") (name "unconnected-(IC1-ACT#-Pad8)") (class "Default")
      (node (ref "IC1") (pin "8") (pinfunction "ACT#_8") (pintype "bidirectional"))
    )
    (net (code "40") (name "unconnected-(IC1-CTS-Pad13)") (class "Default")
      (node (ref "IC1") (pin "13") (pinfunction "CTS_13") (pintype "bidirectional"))
    )
    (net (code "41") (name "unconnected-(IC1-DCD-Pad9)") (class "Default")
      (node (ref "IC1") (pin "9") (pinfunction "DCD_9") (pintype "bidirectional"))
    )
    (net (code "42") (name "unconnected-(IC1-DSR-Pad12)") (class "Default")
      (node (ref "IC1") (pin "12") (pinfunction "DSR_12") (pintype "bidirectional"))
    )
    (net (code "43") (name "unconnected-(IC1-RI-Pad14)") (class "Default")
      (node (ref "IC1") (pin "14") (pinfunction "RI_14") (pintype "bidirectional"))
    )
    (net (code "44") (name "unconnected-(IC3-SD_CLK-Pad21)") (class "Default")
      (node (ref "IC3") (pin "21") (pinfunction "SD_CLK_21") (pintype "bidirectional"))
    )
    (net (code "45") (name "unconnected-(IC3-SD_CMD-Pad20)") (class "Default")
      (node (ref "IC3") (pin "20") (pinfunction "SD_CMD_20") (pintype "bidirectional"))
    )
    (net (code "46") (name "unconnected-(IC3-SD_DATA_0-Pad22)") (class "Default")
      (node (ref "IC3") (pin "22") (pinfunction "SD_DATA_0_22") (pintype "bidirectional"))
    )
    (net (code "47") (name "unconnected-(IC3-SD_DATA_1-Pad23)") (class "Default")
      (node (ref "IC3") (pin "23") (pinfunction "SD_DATA_1_23") (pintype "bidirectional"))
    )
    (net (code "48") (name "unconnected-(IC3-SD_DATA_2-Pad18)") (class "Default")
      (node (ref "IC3") (pin "18") (pinfunction "SD_DATA_2_18") (pintype "bidirectional"))
    )
    (net (code "49") (name "unconnected-(IC3-SD_DATA_3-Pad19)") (class "Default")
      (node (ref "IC3") (pin "19") (pinfunction "SD_DATA_3_19") (pintype "bidirectional"))
    )
    (net (code "50") (name "unconnected-(IC3-TOUT-Pad6)") (class "Default")
      (node (ref "IC3") (pin "6") (pinfunction "TOUT_6") (pintype "bidirectional"))
    )
    (net (code "51") (name "unconnected-(IC3-VDD_RTC-Pad5)") (class "Default")
      (node (ref "IC3") (pin "5") (pinfunction "VDD_RTC_5") (pintype "bidirectional"))
    )
    (net (code "52") (name "unconnected-(IC3-XDP_DCDC-Pad8)") (class "Default")
      (node (ref "IC3") (pin "8") (pinfunction "XDP_DCDC_8") (pintype "bidirectional"))
    )
    (net (code "53") (name "unconnected-(LED1-DO-Pad2-DOUT)") (class "Default")
      (node (ref "LED1") (pin "2-DOUT") (pinfunction "DO_2-DOUT") (pintype "output"))
    )
    (net (code "54") (name "unconnected-(MOD1-PadADC)") (class "Default")
      (node (ref "MOD1") (pin "ADC") (pinfunction "ADC_ADC") (pintype "bidirectional"))
    )
    (net (code "55") (name "unconnected-(MOD1-PadIO16)") (class "Default")
      (node (ref "MOD1") (pin "IO16") (pinfunction "IO16_IO16") (pintype "bidirectional"))
    )
  )
)
